# 50_VO-HDMI2_1_TX.net
KiCad netlist of a schematic drawn in Altium Designer
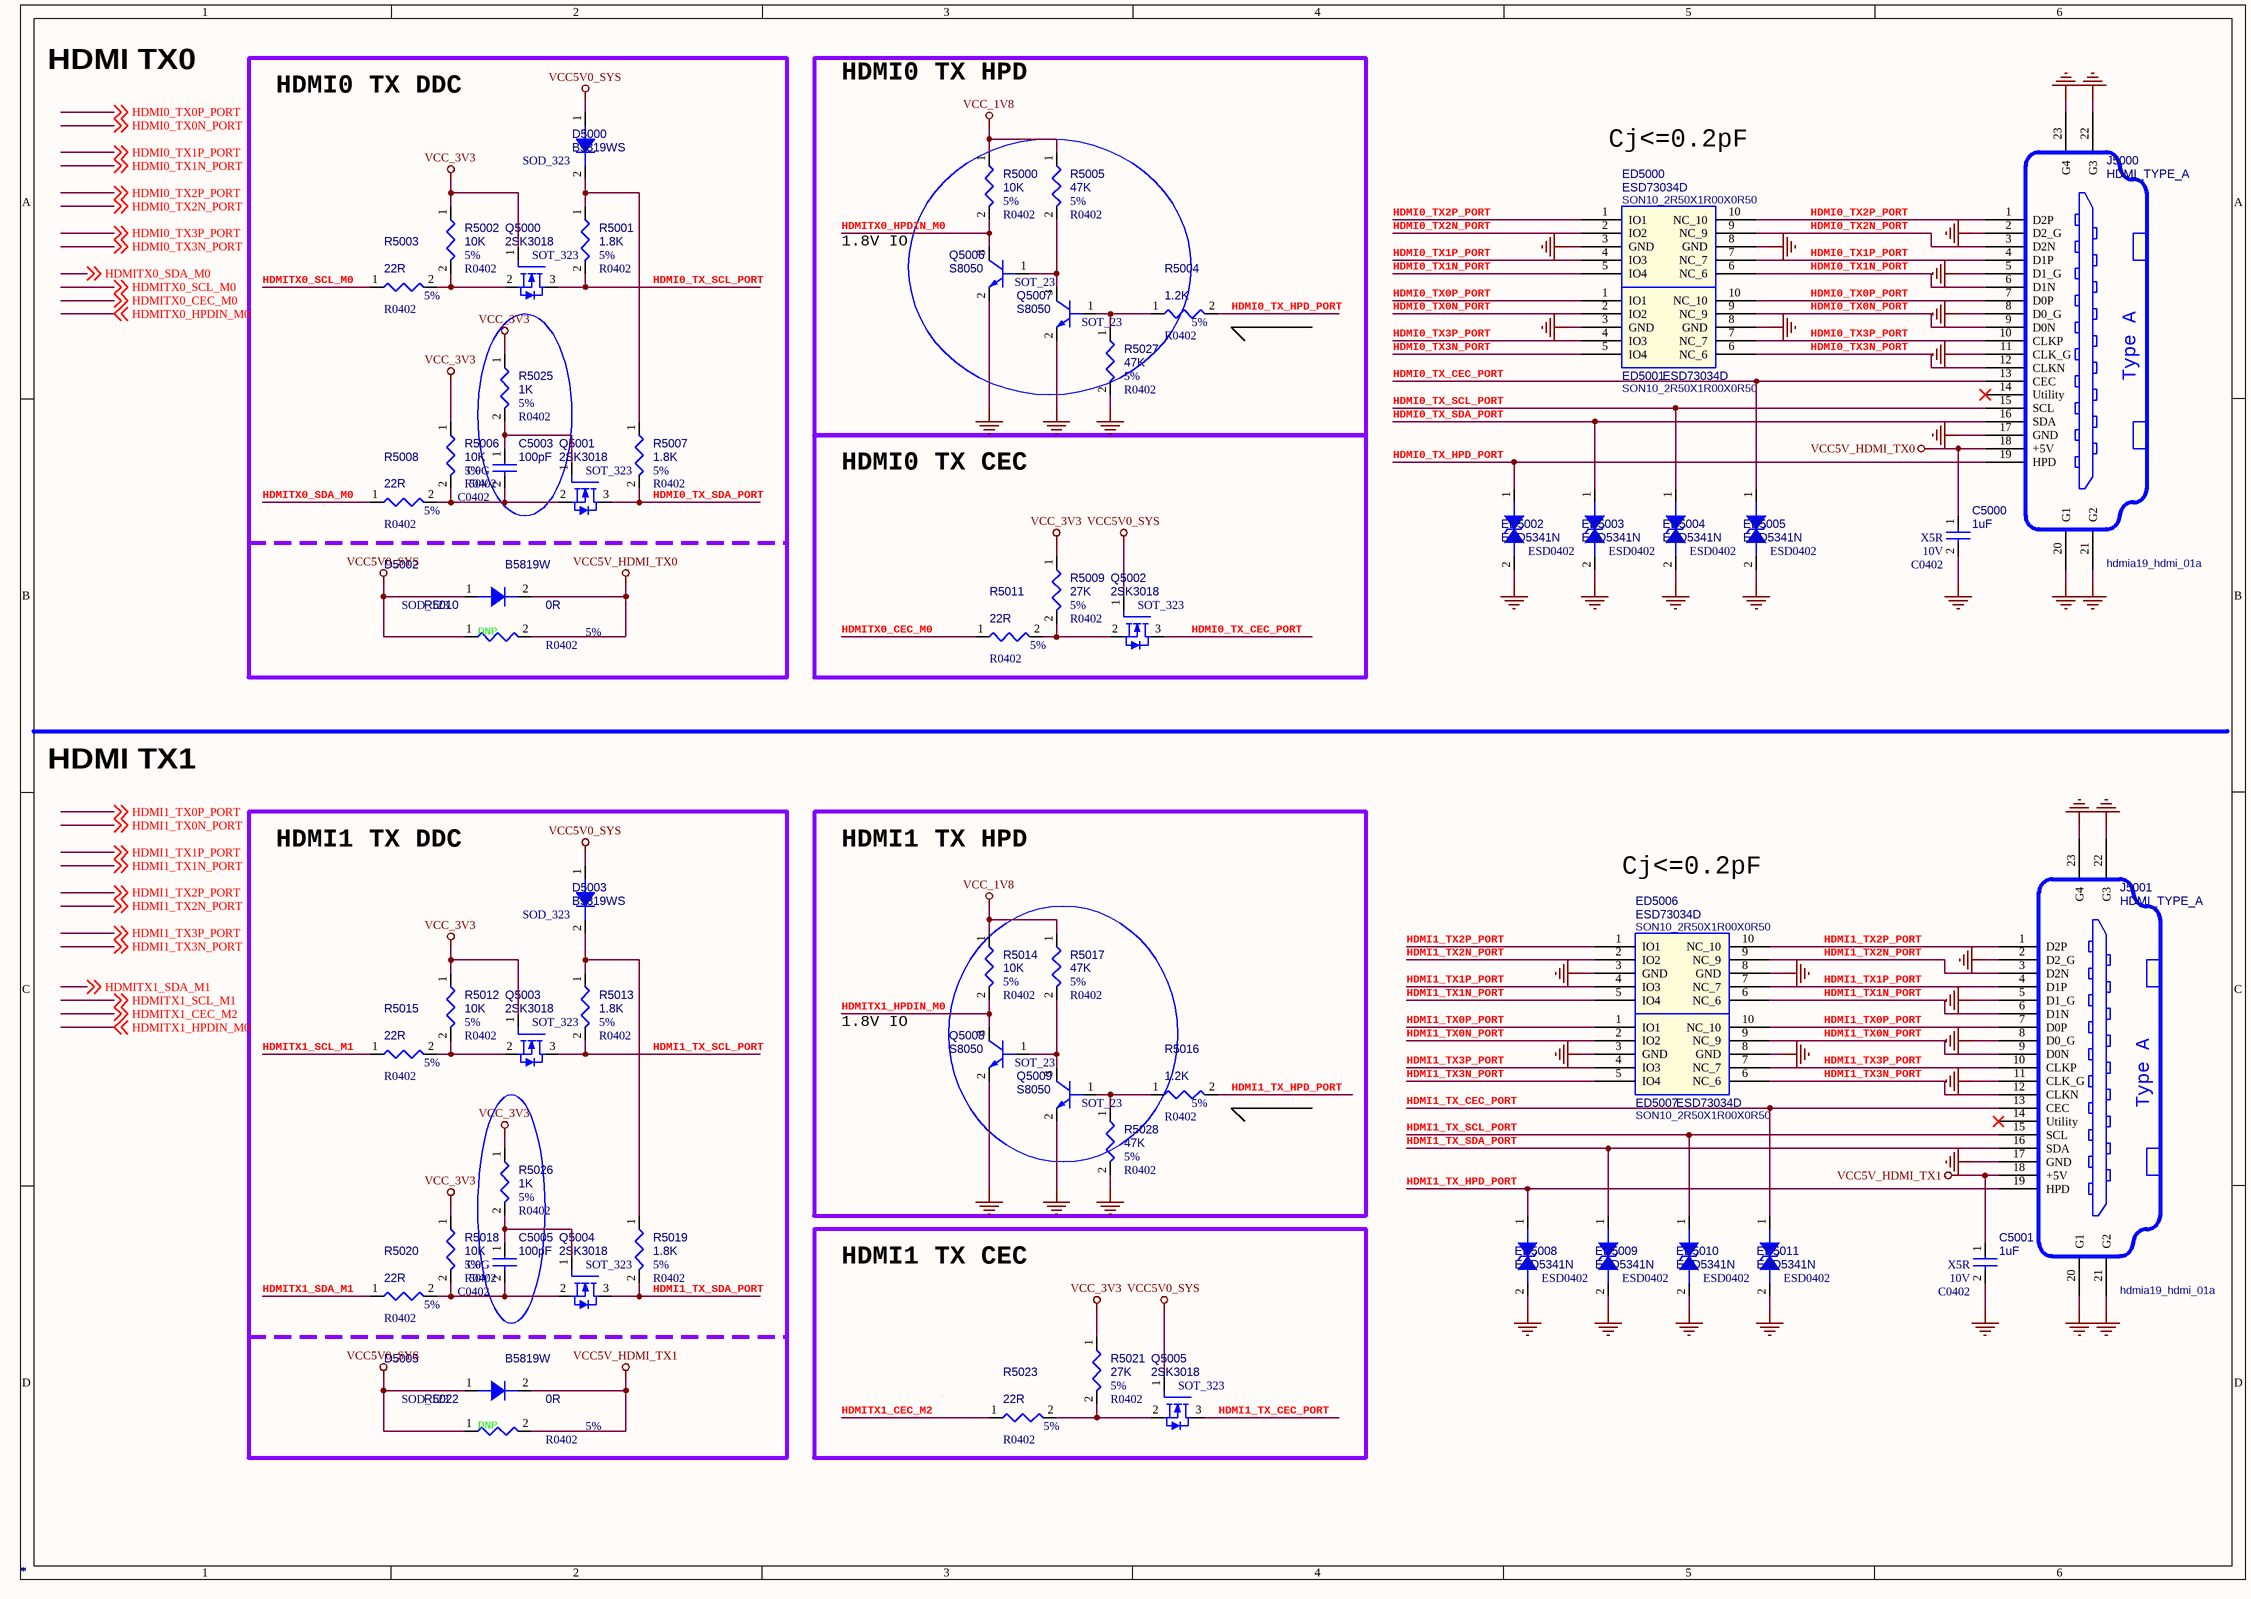
[diagram p0: 50.VO-HDMI2.1 TX.SchDoc]

(export (version "E")
  (design (tool "Eeschema 10.0.6"))
  (components
    (comp (ref "C5000")
      (value "*")
      (footprint "C0402")
      (description "cap,1.00uF,+/-10%,10V,X5R,C0402")
      (fields
        (field (name "VOLTAGE") "10V")
        (field (name "PCB FOOTPRINT") "C0402")
        (field (name "DIELECTRIC") "X5R")
        (field (name "MANUFACTURER") "TDK")
        (field (name "TOLERANCE") "10%")
        (field (name "ALTIUM_UNNAMED_1") "1uF")
        (field (name "CREATED BY") "JJJ")
      )
      (libsource (lib "*") (part "CAP NP"))
    )
    (comp (ref "C5001")
      (value "*")
      (footprint "C0402")
      (description "cap,1.00uF,+/-10%,10V,X5R,C0402")
      (fields
        (field (name "VOLTAGE") "10V")
        (field (name "PCB FOOTPRINT") "C0402")
        (field (name "DIELECTRIC") "X5R")
        (field (name "MANUFACTURER") "TDK")
        (field (name "TOLERANCE") "10%")
        (field (name "ALTIUM_UNNAMED_1") "1uF")
        (field (name "CREATED BY") "JJJ")
      )
      (libsource (lib "*") (part "CAP NP"))
    )
    (comp (ref "C5003")
      (value "*")
      (footprint "C0402")
      (description "cap,100.00pF,+/-10%,50V,C0G,C0402")
      (fields
        (field (name "VOLTAGE") "50V")
        (field (name "PCB FOOTPRINT") "C0402")
        (field (name "DIELECTRIC") "C0G")
        (field (name "TOLERANCE") "10%")
        (field (name "MANUFACTURER") "TDK")
        (field (name "ALTIUM_UNNAMED_1") "100pF")
        (field (name "CREATED BY") "JJJ")
      )
      (libsource (lib "*") (part "CAP NP"))
    )
    (comp (ref "C5005")
      (value "*")
      (footprint "C0402")
      (description "cap,100.00pF,+/-10%,50V,C0G,C0402")
      (fields
        (field (name "VOLTAGE") "50V")
        (field (name "PCB FOOTPRINT") "C0402")
        (field (name "DIELECTRIC") "C0G")
        (field (name "TOLERANCE") "10%")
        (field (name "MANUFACTURER") "TDK")
        (field (name "ALTIUM_UNNAMED_1") "100pF")
        (field (name "CREATED BY") "JJJ")
      )
      (libsource (lib "*") (part "CAP NP"))
    )
    (comp (ref "D5000")
      (value "*")
      (footprint "SOD_323")
      (description "Schottky BarrierЈ¬B5819WS SOD-323")
      (fields
        (field (name "PCB FOOTPRINT") "SOD_323")
        (field (name "MANUFACTURER") "і¤µз")
        (field (name "ALTIUM_UNNAMED_1") "B5819WS")
        (field (name "CREATED BY") "JJJ")
      )
      (libsource (lib "*") (part "DIODE"))
    )
    (comp (ref "D5002")
      (value "*")
      (footprint "SOD_123")
      (description "Schottky BarrierЈ¬B5819W SOD-123")
      (fields
        (field (name "PCB FOOTPRINT") "SOD_123")
        (field (name "MANUFACTURER") "і¤µз")
        (field (name "ALTIUM_UNNAMED_1") "B5819W")
        (field (name "CREATED BY") "JJJ")
      )
      (libsource (lib "*") (part "DIODE"))
    )
    (comp (ref "D5003")
      (value "*")
      (footprint "SOD_323")
      (description "Schottky BarrierЈ¬B5819WS SOD-323")
      (fields
        (field (name "PCB FOOTPRINT") "SOD_323")
        (field (name "MANUFACTURER") "і¤µз")
        (field (name "ALTIUM_UNNAMED_1") "B5819WS")
        (field (name "CREATED BY") "JJJ")
      )
      (libsource (lib "*") (part "DIODE"))
    )
    (comp (ref "D5005")
      (value "*")
      (footprint "SOD_123")
      (description "Schottky BarrierЈ¬B5819W SOD-123")
      (fields
        (field (name "PCB FOOTPRINT") "SOD_123")
        (field (name "MANUFACTURER") "і¤µз")
        (field (name "ALTIUM_UNNAMED_1") "B5819W")
        (field (name "CREATED BY") "JJJ")
      )
      (libsource (lib "*") (part "DIODE"))
    )
    (comp (ref "ED5000")
      (value "*")
      (footprint "SON10_2R50X1R00X0R50")
      (description "4-Lines, Uni-directional, Ultra-low Capacitance Transient Voltage Suppressors")
      (fields
        (field (name "PCB FOOTPRINT") "SON10_2R50X1R00X0R50")
        (field (name "MANUFACTURER") "WillSemi(О¤¶ы°лµјМе)")
        (field (name "ALTIUM_UNNAMED_1") "ESD73034D")
        (field (name "CREATED BY") "JJJ")
      )
      (libsource (lib "*") (part "ESD_ESD5304D"))
    )
    (comp (ref "ED5001")
      (value "*")
      (footprint "SON10_2R50X1R00X0R50")
      (description "4-Lines, Uni-directional, Ultra-low Capacitance Transient Voltage Suppressors")
      (fields
        (field (name "PCB FOOTPRINT") "SON10_2R50X1R00X0R50")
        (field (name "MANUFACTURER") "WillSemi(О¤¶ы°лµјМе)")
        (field (name "ALTIUM_UNNAMED_1") "ESD73034D")
        (field (name "CREATED BY") "JJJ")
      )
      (libsource (lib "*") (part "ESD_ESD5304D"))
    )
    (comp (ref "ED5002")
      (value "*")
      (footprint "ESD0402")
      (description "1-Line, Bi-directional, Transient Voltage Suppressors.1pF.")
      (fields
        (field (name "PCB FOOTPRINT") "ESD0402")
        (field (name "MANUFACTURER") "WillSemi(О¤¶ы°лµјМе)")
        (field (name "ALTIUM_UNNAMED_1") "ESD5341N")
        (field (name "CREATED BY") "JJJ")
      )
      (libsource (lib "*") (part "DIODE BI_DIR TRIG"))
    )
    (comp (ref "ED5003")
      (value "*")
      (footprint "ESD0402")
      (description "1-Line, Bi-directional, Transient Voltage Suppressors.1pF.")
      (fields
        (field (name "PCB FOOTPRINT") "ESD0402")
        (field (name "MANUFACTURER") "WillSemi(О¤¶ы°лµјМе)")
        (field (name "ALTIUM_UNNAMED_1") "ESD5341N")
        (field (name "CREATED BY") "JJJ")
      )
      (libsource (lib "*") (part "DIODE BI_DIR TRIG"))
    )
    (comp (ref "ED5004")
      (value "*")
      (footprint "ESD0402")
      (description "1-Line, Bi-directional, Transient Voltage Suppressors.1pF.")
      (fields
        (field (name "PCB FOOTPRINT") "ESD0402")
        (field (name "MANUFACTURER") "WillSemi(О¤¶ы°лµјМе)")
        (field (name "ALTIUM_UNNAMED_1") "ESD5341N")
        (field (name "CREATED BY") "JJJ")
      )
      (libsource (lib "*") (part "DIODE BI_DIR TRIG"))
    )
    (comp (ref "ED5005")
      (value "*")
      (footprint "ESD0402")
      (description "1-Line, Bi-directional, Transient Voltage Suppressors.1pF.")
      (fields
        (field (name "PCB FOOTPRINT") "ESD0402")
        (field (name "MANUFACTURER") "WillSemi(О¤¶ы°лµјМе)")
        (field (name "ALTIUM_UNNAMED_1") "ESD5341N")
        (field (name "CREATED BY") "JJJ")
      )
      (libsource (lib "*") (part "DIODE BI_DIR TRIG"))
    )
    (comp (ref "ED5006")
      (value "*")
      (footprint "SON10_2R50X1R00X0R50")
      (description "4-Lines, Uni-directional, Ultra-low Capacitance Transient Voltage Suppressors")
      (fields
        (field (name "PCB FOOTPRINT") "SON10_2R50X1R00X0R50")
        (field (name "MANUFACTURER") "WillSemi(О¤¶ы°лµјМе)")
        (field (name "ALTIUM_UNNAMED_1") "ESD73034D")
        (field (name "CREATED BY") "JJJ")
      )
      (libsource (lib "*") (part "ESD_ESD5304D"))
    )
    (comp (ref "ED5007")
      (value "*")
      (footprint "SON10_2R50X1R00X0R50")
      (description "4-Lines, Uni-directional, Ultra-low Capacitance Transient Voltage Suppressors")
      (fields
        (field (name "PCB FOOTPRINT") "SON10_2R50X1R00X0R50")
        (field (name "MANUFACTURER") "WillSemi(О¤¶ы°лµјМе)")
        (field (name "ALTIUM_UNNAMED_1") "ESD73034D")
        (field (name "CREATED BY") "JJJ")
      )
      (libsource (lib "*") (part "ESD_ESD5304D"))
    )
    (comp (ref "ED5008")
      (value "*")
      (footprint "ESD0402")
      (description "1-Line, Bi-directional, Transient Voltage Suppressors.1pF.")
      (fields
        (field (name "PCB FOOTPRINT") "ESD0402")
        (field (name "MANUFACTURER") "WillSemi(О¤¶ы°лµјМе)")
        (field (name "ALTIUM_UNNAMED_1") "ESD5341N")
        (field (name "CREATED BY") "JJJ")
      )
      (libsource (lib "*") (part "DIODE BI_DIR TRIG"))
    )
    (comp (ref "ED5009")
      (value "*")
      (footprint "ESD0402")
      (description "1-Line, Bi-directional, Transient Voltage Suppressors.1pF.")
      (fields
        (field (name "PCB FOOTPRINT") "ESD0402")
        (field (name "MANUFACTURER") "WillSemi(О¤¶ы°лµјМе)")
        (field (name "ALTIUM_UNNAMED_1") "ESD5341N")
        (field (name "CREATED BY") "JJJ")
      )
      (libsource (lib "*") (part "DIODE BI_DIR TRIG"))
    )
    (comp (ref "ED5010")
      (value "*")
      (footprint "ESD0402")
      (description "1-Line, Bi-directional, Transient Voltage Suppressors.1pF.")
      (fields
        (field (name "PCB FOOTPRINT") "ESD0402")
        (field (name "MANUFACTURER") "WillSemi(О¤¶ы°лµјМе)")
        (field (name "ALTIUM_UNNAMED_1") "ESD5341N")
        (field (name "CREATED BY") "JJJ")
      )
      (libsource (lib "*") (part "DIODE BI_DIR TRIG"))
    )
    (comp (ref "ED5011")
      (value "*")
      (footprint "ESD0402")
      (description "1-Line, Bi-directional, Transient Voltage Suppressors.1pF.")
      (fields
        (field (name "PCB FOOTPRINT") "ESD0402")
        (field (name "MANUFACTURER") "WillSemi(О¤¶ы°лµјМе)")
        (field (name "ALTIUM_UNNAMED_1") "ESD5341N")
        (field (name "CREATED BY") "JJJ")
      )
      (libsource (lib "*") (part "DIODE BI_DIR TRIG"))
    )
    (comp (ref "J5000")
      (value "*")
      (footprint "hdmia19_hdmi_01a")
      (fields
        (field (name "PCB FOOTPRINT") "hdmia19_hdmi_01a")
        (field (name "ALTIUM_UNNAMED_1") "HDMI_TYPE_A")
      )
      (libsource (lib "*") (part "HDMI_TYPE_A_0"))
    )
    (comp (ref "J5001")
      (value "*")
      (footprint "hdmia19_hdmi_01a")
      (fields
        (field (name "PCB FOOTPRINT") "hdmia19_hdmi_01a")
        (field (name "ALTIUM_UNNAMED_1") "HDMI_TYPE_A")
      )
      (libsource (lib "*") (part "HDMI_TYPE_A_0"))
    )
    (comp (ref "Q5000")
      (value "*")
      (footprint "SOT23")
      (description "NMOS,2SK3018,SOT_323,Id=0.1A,Vds=30V")
      (fields
        (field (name "PCB FOOTPRINT") "SOT_323")
        (field (name "MANUFACTURER") "ROHM")
        (field (name "ALTIUM_UNNAMED_1") "2SK3018")
        (field (name "CREATED BY") "JJJ")
      )
      (libsource (lib "*") (part "MOSFET N"))
    )
    (comp (ref "Q5001")
      (value "*")
      (footprint "SOT23")
      (description "NMOS,2SK3018,SOT_323,Id=0.1A,Vds=30V")
      (fields
        (field (name "PCB FOOTPRINT") "SOT_323")
        (field (name "MANUFACTURER") "ROHM")
        (field (name "ALTIUM_UNNAMED_1") "2SK3018")
        (field (name "CREATED BY") "JJJ")
      )
      (libsource (lib "*") (part "MOSFET N"))
    )
    (comp (ref "Q5002")
      (value "*")
      (footprint "SOT23")
      (description "NMOS,2SK3018,SOT_323,Id=0.1A,Vds=30V")
      (fields
        (field (name "PCB FOOTPRINT") "SOT_323")
        (field (name "MANUFACTURER") "ROHM")
        (field (name "ALTIUM_UNNAMED_1") "2SK3018")
        (field (name "CREATED BY") "JJJ")
      )
      (libsource (lib "*") (part "MOSFET N"))
    )
    (comp (ref "Q5003")
      (value "*")
      (footprint "SOT23")
      (description "NMOS,2SK3018,SOT_323,Id=0.1A,Vds=30V")
      (fields
        (field (name "PCB FOOTPRINT") "SOT_323")
        (field (name "MANUFACTURER") "ROHM")
        (field (name "ALTIUM_UNNAMED_1") "2SK3018")
        (field (name "CREATED BY") "JJJ")
      )
      (libsource (lib "*") (part "MOSFET N"))
    )
    (comp (ref "Q5004")
      (value "*")
      (footprint "SOT23")
      (description "NMOS,2SK3018,SOT_323,Id=0.1A,Vds=30V")
      (fields
        (field (name "PCB FOOTPRINT") "SOT_323")
        (field (name "MANUFACTURER") "ROHM")
        (field (name "ALTIUM_UNNAMED_1") "2SK3018")
        (field (name "CREATED BY") "JJJ")
      )
      (libsource (lib "*") (part "MOSFET N"))
    )
    (comp (ref "Q5005")
      (value "*")
      (footprint "SOT23")
      (description "NMOS,2SK3018,SOT_323,Id=0.1A,Vds=30V")
      (fields
        (field (name "PCB FOOTPRINT") "SOT_323")
        (field (name "MANUFACTURER") "ROHM")
        (field (name "ALTIUM_UNNAMED_1") "2SK3018")
        (field (name "CREATED BY") "JJJ")
      )
      (libsource (lib "*") (part "MOSFET N"))
    )
    (comp (ref "Q5006")
      (value "*")
      (footprint "SOT_23")
      (description "S8050,SOT23")
      (fields
        (field (name "PCB FOOTPRINT") "SOT_23")
        (field (name "MANUFACTURER") "і¤µз")
        (field (name "ALTIUM_UNNAMED_1") "S8050")
        (field (name "CREATED BY") "JJJ")
      )
      (libsource (lib "*") (part "NPN"))
    )
    (comp (ref "Q5007")
      (value "*")
      (footprint "SOT_23")
      (description "S8050,SOT23")
      (fields
        (field (name "PCB FOOTPRINT") "SOT_23")
        (field (name "MANUFACTURER") "і¤µз")
        (field (name "ALTIUM_UNNAMED_1") "S8050")
        (field (name "CREATED BY") "JJJ")
      )
      (libsource (lib "*") (part "NPN"))
    )
    (comp (ref "Q5008")
      (value "*")
      (footprint "SOT_23")
      (description "S8050,SOT23")
      (fields
        (field (name "PCB FOOTPRINT") "SOT_23")
        (field (name "MANUFACTURER") "і¤µз")
        (field (name "ALTIUM_UNNAMED_1") "S8050")
        (field (name "CREATED BY") "JJJ")
      )
      (libsource (lib "*") (part "NPN"))
    )
    (comp (ref "Q5009")
      (value "*")
      (footprint "SOT_23")
      (description "S8050,SOT23")
      (fields
        (field (name "PCB FOOTPRINT") "SOT_23")
        (field (name "MANUFACTURER") "і¤µз")
        (field (name "ALTIUM_UNNAMED_1") "S8050")
        (field (name "CREATED BY") "JJJ")
      )
      (libsource (lib "*") (part "NPN"))
    )
    (comp (ref "R5000")
      (value "*")
      (footprint "R0402")
      (description "НЁУГєсД¤µзЧи,10K,+/-5%,R0402,1/16W.")
      (fields
        (field (name "PCB FOOTPRINT") "R0402")
        (field (name "TOLERANCE") "5%")
        (field (name "MANUFACTURER") "YAGEO")
        (field (name "ALTIUM_UNNAMED_1") "10K")
        (field (name "CREATED BY") "YTL")
      )
      (libsource (lib "*") (part "RESISTOR_Dup1"))
    )
    (comp (ref "R5001")
      (value "*")
      (footprint "R0402")
      (description "НЁУГєсД¤µзЧи,1K8,+/-5%,R0402,1/16W.")
      (fields
        (field (name "PCB FOOTPRINT") "R0402")
        (field (name "TOLERANCE") "5%")
        (field (name "MANUFACTURER") "YAGEO")
        (field (name "ALTIUM_UNNAMED_1") "1.8K")
        (field (name "CREATED BY") "YTL")
      )
      (libsource (lib "*") (part "RESISTOR_Dup1"))
    )
    (comp (ref "R5002")
      (value "*")
      (footprint "R0402")
      (description "НЁУГєсД¤µзЧи,10K,+/-5%,R0402,1/16W.")
      (fields
        (field (name "PCB FOOTPRINT") "R0402")
        (field (name "TOLERANCE") "5%")
        (field (name "MANUFACTURER") "YAGEO")
        (field (name "ALTIUM_UNNAMED_1") "10K")
        (field (name "CREATED BY") "YTL")
      )
      (libsource (lib "*") (part "RESISTOR_Dup1"))
    )
    (comp (ref "R5003")
      (value "*")
      (footprint "R0402")
      (description "НЁУГєсД¤µзЧи,22R,+/-5%,R0402,1/16W.")
      (fields
        (field (name "PCB FOOTPRINT") "R0402")
        (field (name "TOLERANCE") "5%")
        (field (name "MANUFACTURER") "YAGEO")
        (field (name "ALTIUM_UNNAMED_1") "22R")
        (field (name "CREATED BY") "YTL")
      )
      (libsource (lib "*") (part "RESISTOR_Dup1"))
    )
    (comp (ref "R5004")
      (value "*")
      (footprint "R0402")
      (description "НЁУГєсД¤µзЧи,1K2,+/-5%,R0402,1/16W.")
      (fields
        (field (name "PCB FOOTPRINT") "R0402")
        (field (name "TOLERANCE") "5%")
        (field (name "MANUFACTURER") "YAGEO")
        (field (name "ALTIUM_UNNAMED_1") "1.2K")
        (field (name "CREATED BY") "YTL")
      )
      (libsource (lib "*") (part "RESISTOR_Dup1"))
    )
    (comp (ref "R5005")
      (value "*")
      (footprint "R0402")
      (description "НЁУГєсД¤µзЧи,47K,+/-5%,R0402,1/16W.")
      (fields
        (field (name "PCB FOOTPRINT") "R0402")
        (field (name "TOLERANCE") "5%")
        (field (name "MANUFACTURER") "YAGEO")
        (field (name "ALTIUM_UNNAMED_1") "47K")
        (field (name "CREATED BY") "YTL")
      )
      (libsource (lib "*") (part "RESISTOR_Dup1"))
    )
    (comp (ref "R5006")
      (value "*")
      (footprint "R0402")
      (description "НЁУГєсД¤µзЧи,10K,+/-5%,R0402,1/16W.")
      (fields
        (field (name "PCB FOOTPRINT") "R0402")
        (field (name "TOLERANCE") "5%")
        (field (name "MANUFACTURER") "YAGEO")
        (field (name "ALTIUM_UNNAMED_1") "10K")
        (field (name "CREATED BY") "YTL")
      )
      (libsource (lib "*") (part "RESISTOR_Dup1"))
    )
    (comp (ref "R5007")
      (value "*")
      (footprint "R0402")
      (description "НЁУГєсД¤µзЧи,1K8,+/-5%,R0402,1/16W.")
      (fields
        (field (name "PCB FOOTPRINT") "R0402")
        (field (name "TOLERANCE") "5%")
        (field (name "MANUFACTURER") "YAGEO")
        (field (name "ALTIUM_UNNAMED_1") "1.8K")
        (field (name "CREATED BY") "YTL")
      )
      (libsource (lib "*") (part "RESISTOR_Dup1"))
    )
    (comp (ref "R5008")
      (value "*")
      (footprint "R0402")
      (description "НЁУГєсД¤µзЧи,22R,+/-5%,R0402,1/16W.")
      (fields
        (field (name "PCB FOOTPRINT") "R0402")
        (field (name "TOLERANCE") "5%")
        (field (name "MANUFACTURER") "YAGEO")
        (field (name "ALTIUM_UNNAMED_1") "22R")
        (field (name "CREATED BY") "YTL")
      )
      (libsource (lib "*") (part "RESISTOR_Dup1"))
    )
    (comp (ref "R5009")
      (value "*")
      (footprint "R0402")
      (description "НЁУГєсД¤µзЧи,27K,+/-5%,R0402,1/16W.")
      (fields
        (field (name "PCB FOOTPRINT") "R0402")
        (field (name "TOLERANCE") "5%")
        (field (name "MANUFACTURER") "YAGEO")
        (field (name "ALTIUM_UNNAMED_1") "27K")
        (field (name "CREATED BY") "YTL")
      )
      (libsource (lib "*") (part "RESISTOR_Dup1"))
    )
    (comp (ref "R5010")
      (value "*")
      (footprint "R0402")
      (description "НЁУГєсД¤µзЧи,0R,+/-5%,R0402,1/16W.")
      (fields
        (field (name "PCB FOOTPRINT") "R0402")
        (field (name "TOLERANCE") "5%")
        (field (name "OPTION") "DNP")
        (field (name "MANUFACTURER") "YAGEO")
        (field (name "ALTIUM_UNNAMED_1") "0R")
        (field (name "CREATED BY") "YTL")
      )
      (libsource (lib "*") (part "RESISTOR_Dup1"))
    )
    (comp (ref "R5011")
      (value "*")
      (footprint "R0402")
      (description "НЁУГєсД¤µзЧи,22R,+/-5%,R0402,1/16W.")
      (fields
        (field (name "PCB FOOTPRINT") "R0402")
        (field (name "TOLERANCE") "5%")
        (field (name "MANUFACTURER") "YAGEO")
        (field (name "ALTIUM_UNNAMED_1") "22R")
        (field (name "CREATED BY") "YTL")
      )
      (libsource (lib "*") (part "RESISTOR_Dup1"))
    )
    (comp (ref "R5012")
      (value "*")
      (footprint "R0402")
      (description "НЁУГєсД¤µзЧи,10K,+/-5%,R0402,1/16W.")
      (fields
        (field (name "PCB FOOTPRINT") "R0402")
        (field (name "TOLERANCE") "5%")
        (field (name "MANUFACTURER") "YAGEO")
        (field (name "ALTIUM_UNNAMED_1") "10K")
        (field (name "CREATED BY") "YTL")
      )
      (libsource (lib "*") (part "RESISTOR_Dup1"))
    )
    (comp (ref "R5013")
      (value "*")
      (footprint "R0402")
      (description "НЁУГєсД¤µзЧи,1K8,+/-5%,R0402,1/16W.")
      (fields
        (field (name "PCB FOOTPRINT") "R0402")
        (field (name "TOLERANCE") "5%")
        (field (name "MANUFACTURER") "YAGEO")
        (field (name "ALTIUM_UNNAMED_1") "1.8K")
        (field (name "CREATED BY") "YTL")
      )
      (libsource (lib "*") (part "RESISTOR_Dup1"))
    )
    (comp (ref "R5014")
      (value "*")
      (footprint "R0402")
      (description "НЁУГєсД¤µзЧи,10K,+/-5%,R0402,1/16W.")
      (fields
        (field (name "PCB FOOTPRINT") "R0402")
        (field (name "TOLERANCE") "5%")
        (field (name "MANUFACTURER") "YAGEO")
        (field (name "ALTIUM_UNNAMED_1") "10K")
        (field (name "CREATED BY") "YTL")
      )
      (libsource (lib "*") (part "RESISTOR_Dup1"))
    )
    (comp (ref "R5015")
      (value "*")
      (footprint "R0402")
      (description "НЁУГєсД¤µзЧи,22R,+/-5%,R0402,1/16W.")
      (fields
        (field (name "PCB FOOTPRINT") "R0402")
        (field (name "TOLERANCE") "5%")
        (field (name "MANUFACTURER") "YAGEO")
        (field (name "ALTIUM_UNNAMED_1") "22R")
        (field (name "CREATED BY") "YTL")
      )
      (libsource (lib "*") (part "RESISTOR_Dup1"))
    )
    (comp (ref "R5016")
      (value "*")
      (footprint "R0402")
      (description "НЁУГєсД¤µзЧи,1K2,+/-5%,R0402,1/16W.")
      (fields
        (field (name "PCB FOOTPRINT") "R0402")
        (field (name "TOLERANCE") "5%")
        (field (name "MANUFACTURER") "YAGEO")
        (field (name "ALTIUM_UNNAMED_1") "1.2K")
        (field (name "CREATED BY") "YTL")
      )
      (libsource (lib "*") (part "RESISTOR_Dup1"))
    )
    (comp (ref "R5017")
      (value "*")
      (footprint "R0402")
      (description "НЁУГєсД¤µзЧи,47K,+/-5%,R0402,1/16W.")
      (fields
        (field (name "PCB FOOTPRINT") "R0402")
        (field (name "TOLERANCE") "5%")
        (field (name "MANUFACTURER") "YAGEO")
        (field (name "ALTIUM_UNNAMED_1") "47K")
        (field (name "CREATED BY") "YTL")
      )
      (libsource (lib "*") (part "RESISTOR_Dup1"))
    )
    (comp (ref "R5018")
      (value "*")
      (footprint "R0402")
      (description "НЁУГєсД¤µзЧи,10K,+/-5%,R0402,1/16W.")
      (fields
        (field (name "PCB FOOTPRINT") "R0402")
        (field (name "TOLERANCE") "5%")
        (field (name "MANUFACTURER") "YAGEO")
        (field (name "ALTIUM_UNNAMED_1") "10K")
        (field (name "CREATED BY") "YTL")
      )
      (libsource (lib "*") (part "RESISTOR_Dup1"))
    )
    (comp (ref "R5019")
      (value "*")
      (footprint "R0402")
      (description "НЁУГєсД¤µзЧи,1K8,+/-5%,R0402,1/16W.")
      (fields
        (field (name "PCB FOOTPRINT") "R0402")
        (field (name "TOLERANCE") "5%")
        (field (name "MANUFACTURER") "YAGEO")
        (field (name "ALTIUM_UNNAMED_1") "1.8K")
        (field (name "CREATED BY") "YTL")
      )
      (libsource (lib "*") (part "RESISTOR_Dup1"))
    )
    (comp (ref "R5020")
      (value "*")
      (footprint "R0402")
      (description "НЁУГєсД¤µзЧи,22R,+/-5%,R0402,1/16W.")
      (fields
        (field (name "PCB FOOTPRINT") "R0402")
        (field (name "TOLERANCE") "5%")
        (field (name "MANUFACTURER") "YAGEO")
        (field (name "ALTIUM_UNNAMED_1") "22R")
        (field (name "CREATED BY") "YTL")
      )
      (libsource (lib "*") (part "RESISTOR_Dup1"))
    )
    (comp (ref "R5021")
      (value "*")
      (footprint "R0402")
      (description "НЁУГєсД¤µзЧи,27K,+/-5%,R0402,1/16W.")
      (fields
        (field (name "PCB FOOTPRINT") "R0402")
        (field (name "TOLERANCE") "5%")
        (field (name "MANUFACTURER") "YAGEO")
        (field (name "ALTIUM_UNNAMED_1") "27K")
        (field (name "CREATED BY") "YTL")
      )
      (libsource (lib "*") (part "RESISTOR_Dup1"))
    )
    (comp (ref "R5022")
      (value "*")
      (footprint "R0402")
      (description "НЁУГєсД¤µзЧи,0R,+/-5%,R0402,1/16W.")
      (fields
        (field (name "PCB FOOTPRINT") "R0402")
        (field (name "TOLERANCE") "5%")
        (field (name "OPTION") "DNP")
        (field (name "MANUFACTURER") "YAGEO")
        (field (name "ALTIUM_UNNAMED_1") "0R")
        (field (name "CREATED BY") "YTL")
      )
      (libsource (lib "*") (part "RESISTOR_Dup1"))
    )
    (comp (ref "R5023")
      (value "*")
      (footprint "R0402")
      (description "НЁУГєсД¤µзЧи,22R,+/-5%,R0402,1/16W.")
      (fields
        (field (name "PCB FOOTPRINT") "R0402")
        (field (name "TOLERANCE") "5%")
        (field (name "MANUFACTURER") "YAGEO")
        (field (name "ALTIUM_UNNAMED_1") "22R")
        (field (name "CREATED BY") "YTL")
      )
      (libsource (lib "*") (part "RESISTOR_Dup1"))
    )
    (comp (ref "R5025")
      (value "*")
      (footprint "R0402")
      (description "НЁУГєсД¤µзЧи,1K,+/-5%,R0402,1/16W.")
      (fields
        (field (name "PCB FOOTPRINT") "R0402")
        (field (name "TOLERANCE") "5%")
        (field (name "MANUFACTURER") "YAGEO")
        (field (name "ALTIUM_UNNAMED_1") "1K")
        (field (name "CREATED BY") "YTL")
      )
      (libsource (lib "*") (part "RESISTOR_Dup1"))
    )
    (comp (ref "R5026")
      (value "*")
      (footprint "R0402")
      (description "НЁУГєсД¤µзЧи,1K,+/-5%,R0402,1/16W.")
      (fields
        (field (name "PCB FOOTPRINT") "R0402")
        (field (name "TOLERANCE") "5%")
        (field (name "MANUFACTURER") "YAGEO")
        (field (name "ALTIUM_UNNAMED_1") "1K")
        (field (name "CREATED BY") "YTL")
      )
      (libsource (lib "*") (part "RESISTOR_Dup1"))
    )
    (comp (ref "R5027")
      (value "*")
      (footprint "R0402")
      (description "НЁУГєсД¤µзЧи,47K,+/-5%,R0402,1/16W.")
      (fields
        (field (name "PCB FOOTPRINT") "R0402")
        (field (name "TOLERANCE") "5%")
        (field (name "MANUFACTURER") "YAGEO")
        (field (name "ALTIUM_UNNAMED_1") "47K")
        (field (name "CREATED BY") "YTL")
      )
      (libsource (lib "*") (part "RESISTOR_Dup1"))
    )
    (comp (ref "R5028")
      (value "*")
      (footprint "R0402")
      (description "НЁУГєсД¤µзЧи,47K,+/-5%,R0402,1/16W.")
      (fields
        (field (name "PCB FOOTPRINT") "R0402")
        (field (name "TOLERANCE") "5%")
        (field (name "MANUFACTURER") "YAGEO")
        (field (name "ALTIUM_UNNAMED_1") "47K")
        (field (name "CREATED BY") "YTL")
      )
      (libsource (lib "*") (part "RESISTOR_Dup1"))
    )
  )
  (nets
    (net (code "1") (name "/HDMI0_TX_CEC_PORT") (class "Default")
      (node (ref "ED5005") (pin "1") (pinfunction "1_1") (pintype "passive"))
      (node (ref "J5000") (pin "13") (pinfunction "CEC_13") (pintype "passive"))
      (node (ref "Q5002") (pin "3") (pinfunction "DRAIN_3") (pintype "passive"))
    )
    (net (code "2") (name "/HDMI0_TX_HPD_PORT") (class "Default")
      (node (ref "ED5002") (pin "1") (pinfunction "1_1") (pintype "passive"))
      (node (ref "J5000") (pin "19") (pinfunction "HPD_19") (pintype "passive"))
      (node (ref "R5004") (pin "2") (pinfunction "2_2") (pintype "passive"))
    )
    (net (code "3") (name "/HDMI0_TX_SCL_PORT") (class "Default")
      (node (ref "ED5004") (pin "1") (pinfunction "1_1") (pintype "passive"))
      (node (ref "J5000") (pin "15") (pinfunction "SCL_15") (pintype "passive"))
      (node (ref "Q5000") (pin "3") (pinfunction "DRAIN_3") (pintype "passive"))
      (node (ref "R5001") (pin "2") (pinfunction "2_2") (pintype "passive"))
    )
    (net (code "4") (name "/HDMI0_TX_SDA_PORT") (class "Default")
      (node (ref "ED5003") (pin "1") (pinfunction "1_1") (pintype "passive"))
      (node (ref "J5000") (pin "16") (pinfunction "SDA_16") (pintype "passive"))
      (node (ref "Q5001") (pin "3") (pinfunction "DRAIN_3") (pintype "passive"))
      (node (ref "R5007") (pin "2") (pinfunction "2_2") (pintype "passive"))
    )
    (net (code "5") (name "/HDMI1_TX_CEC_PORT") (class "Default")
      (node (ref "ED5011") (pin "1") (pinfunction "1_1") (pintype "passive"))
      (node (ref "J5001") (pin "13") (pinfunction "CEC_13") (pintype "passive"))
      (node (ref "Q5005") (pin "3") (pinfunction "DRAIN_3") (pintype "passive"))
    )
    (net (code "6") (name "/HDMI1_TX_HPD_PORT") (class "Default")
      (node (ref "ED5008") (pin "1") (pinfunction "1_1") (pintype "passive"))
      (node (ref "J5001") (pin "19") (pinfunction "HPD_19") (pintype "passive"))
      (node (ref "R5016") (pin "2") (pinfunction "2_2") (pintype "passive"))
    )
    (net (code "7") (name "/HDMI1_TX_SCL_PORT") (class "Default")
      (node (ref "ED5010") (pin "1") (pinfunction "1_1") (pintype "passive"))
      (node (ref "J5001") (pin "15") (pinfunction "SCL_15") (pintype "passive"))
      (node (ref "Q5003") (pin "3") (pinfunction "DRAIN_3") (pintype "passive"))
      (node (ref "R5013") (pin "2") (pinfunction "2_2") (pintype "passive"))
    )
    (net (code "8") (name "/HDMI1_TX_SDA_PORT") (class "Default")
      (node (ref "ED5009") (pin "1") (pinfunction "1_1") (pintype "passive"))
      (node (ref "J5001") (pin "16") (pinfunction "SDA_16") (pintype "passive"))
      (node (ref "Q5004") (pin "3") (pinfunction "DRAIN_3") (pintype "passive"))
      (node (ref "R5019") (pin "2") (pinfunction "2_2") (pintype "passive"))
    )
    (net (code "9") (name "GND") (class "Default")
      (node (ref "C5000") (pin "2") (pinfunction "2_2") (pintype "passive"))
      (node (ref "C5001") (pin "2") (pinfunction "2_2") (pintype "passive"))
      (node (ref "ED5000") (pin "3") (pinfunction "GND_3") (pintype "power_in"))
      (node (ref "ED5000") (pin "8") (pinfunction "GND_8") (pintype "power_in"))
      (node (ref "ED5001") (pin "3") (pinfunction "GND_3") (pintype "power_in"))
      (node (ref "ED5001") (pin "8") (pinfunction "GND_8") (pintype "power_in"))
      (node (ref "ED5002") (pin "2") (pinfunction "2_2") (pintype "passive"))
      (node (ref "ED5003") (pin "2") (pinfunction "2_2") (pintype "passive"))
      (node (ref "ED5004") (pin "2") (pinfunction "2_2") (pintype "passive"))
      (node (ref "ED5005") (pin "2") (pinfunction "2_2") (pintype "passive"))
      (node (ref "ED5006") (pin "3") (pinfunction "GND_3") (pintype "power_in"))
      (node (ref "ED5006") (pin "8") (pinfunction "GND_8") (pintype "power_in"))
      (node (ref "ED5007") (pin "3") (pinfunction "GND_3") (pintype "power_in"))
      (node (ref "ED5007") (pin "8") (pinfunction "GND_8") (pintype "power_in"))
      (node (ref "ED5008") (pin "2") (pinfunction "2_2") (pintype "passive"))
      (node (ref "ED5009") (pin "2") (pinfunction "2_2") (pintype "passive"))
      (node (ref "ED5010") (pin "2") (pinfunction "2_2") (pintype "passive"))
      (node (ref "ED5011") (pin "2") (pinfunction "2_2") (pintype "passive"))
      (node (ref "J5000") (pin "11") (pinfunction "CLK_G_11") (pintype "passive"))
      (node (ref "J5000") (pin "17") (pinfunction "GND_17") (pintype "passive"))
      (node (ref "J5000") (pin "2") (pinfunction "D2_G_2") (pintype "passive"))
      (node (ref "J5000") (pin "20") (pinfunction "G1_20") (pintype "passive"))
      (node (ref "J5000") (pin "21") (pinfunction "G2_21") (pintype "passive"))
      (node (ref "J5000") (pin "22") (pinfunction "G3_22") (pintype "passive"))
      (node (ref "J5000") (pin "23") (pinfunction "G4_23") (pintype "passive"))
      (node (ref "J5000") (pin "5") (pinfunction "D1_G_5") (pintype "passive"))
      (node (ref "J5000") (pin "8") (pinfunction "D0_G_8") (pintype "passive"))
      (node (ref "J5001") (pin "11") (pinfunction "CLK_G_11") (pintype "passive"))
      (node (ref "J5001") (pin "17") (pinfunction "GND_17") (pintype "passive"))
      (node (ref "J5001") (pin "2") (pinfunction "D2_G_2") (pintype "passive"))
      (node (ref "J5001") (pin "20") (pinfunction "G1_20") (pintype "passive"))
      (node (ref "J5001") (pin "21") (pinfunction "G2_21") (pintype "passive"))
      (node (ref "J5001") (pin "22") (pinfunction "G3_22") (pintype "passive"))
      (node (ref "J5001") (pin "23") (pinfunction "G4_23") (pintype "passive"))
      (node (ref "J5001") (pin "5") (pinfunction "D1_G_5") (pintype "passive"))
      (node (ref "J5001") (pin "8") (pinfunction "D0_G_8") (pintype "passive"))
      (node (ref "Q5006") (pin "2") (pinfunction "EMITTER_2") (pintype "passive"))
      (node (ref "Q5007") (pin "2") (pinfunction "EMITTER_2") (pintype "passive"))
      (node (ref "Q5008") (pin "2") (pinfunction "EMITTER_2") (pintype "passive"))
      (node (ref "Q5009") (pin "2") (pinfunction "EMITTER_2") (pintype "passive"))
      (node (ref "R5027") (pin "2") (pinfunction "2_2") (pintype "passive"))
      (node (ref "R5028") (pin "2") (pinfunction "2_2") (pintype "passive"))
    )
    (net (code "10") (name "HDMI0_TX0N_PORT") (class "Default")
      (node (ref "ED5001") (pin "2") (pinfunction "IO2_2") (pintype "passive"))
      (node (ref "ED5001") (pin "9") (pinfunction "NC_9_9") (pintype "passive"))
      (node (ref "J5000") (pin "9") (pinfunction "D0N_9") (pintype "passive"))
    )
    (net (code "11") (name "HDMI0_TX0P_PORT") (class "Default")
      (node (ref "ED5001") (pin "1") (pinfunction "IO1_1") (pintype "passive"))
      (node (ref "ED5001") (pin "10") (pinfunction "NC_10_10") (pintype "passive"))
      (node (ref "J5000") (pin "7") (pinfunction "D0P_7") (pintype "passive"))
    )
    (net (code "12") (name "HDMI0_TX1N_PORT") (class "Default")
      (node (ref "ED5000") (pin "5") (pinfunction "IO4_5") (pintype "passive"))
      (node (ref "ED5000") (pin "6") (pinfunction "NC_6_6") (pintype "passive"))
      (node (ref "J5000") (pin "6") (pinfunction "D1N_6") (pintype "passive"))
    )
    (net (code "13") (name "HDMI0_TX1P_PORT") (class "Default")
      (node (ref "ED5000") (pin "4") (pinfunction "IO3_4") (pintype "passive"))
      (node (ref "ED5000") (pin "7") (pinfunction "NC_7_7") (pintype "passive"))
      (node (ref "J5000") (pin "4") (pinfunction "D1P_4") (pintype "passive"))
    )
    (net (code "14") (name "HDMI0_TX2N_PORT") (class "Default")
      (node (ref "ED5000") (pin "2") (pinfunction "IO2_2") (pintype "passive"))
      (node (ref "ED5000") (pin "9") (pinfunction "NC_9_9") (pintype "passive"))
      (node (ref "J5000") (pin "3") (pinfunction "D2N_3") (pintype "passive"))
    )
    (net (code "15") (name "HDMI0_TX2P_PORT") (class "Default")
      (node (ref "ED5000") (pin "1") (pinfunction "IO1_1") (pintype "passive"))
      (node (ref "ED5000") (pin "10") (pinfunction "NC_10_10") (pintype "passive"))
      (node (ref "J5000") (pin "1") (pinfunction "D2P_1") (pintype "passive"))
    )
    (net (code "16") (name "HDMI0_TX3N_PORT") (class "Default")
      (node (ref "ED5001") (pin "5") (pinfunction "IO4_5") (pintype "passive"))
      (node (ref "ED5001") (pin "6") (pinfunction "NC_6_6") (pintype "passive"))
      (node (ref "J5000") (pin "12") (pinfunction "CLKN_12") (pintype "passive"))
    )
    (net (code "17") (name "HDMI0_TX3P_PORT") (class "Default")
      (node (ref "ED5001") (pin "4") (pinfunction "IO3_4") (pintype "passive"))
      (node (ref "ED5001") (pin "7") (pinfunction "NC_7_7") (pintype "passive"))
      (node (ref "J5000") (pin "10") (pinfunction "CLKP_10") (pintype "passive"))
    )
    (net (code "18") (name "HDMI1_TX0N_PORT") (class "Default")
      (node (ref "ED5007") (pin "2") (pinfunction "IO2_2") (pintype "passive"))
      (node (ref "ED5007") (pin "9") (pinfunction "NC_9_9") (pintype "passive"))
      (node (ref "J5001") (pin "9") (pinfunction "D0N_9") (pintype "passive"))
    )
    (net (code "19") (name "HDMI1_TX0P_PORT") (class "Default")
      (node (ref "ED5007") (pin "1") (pinfunction "IO1_1") (pintype "passive"))
      (node (ref "ED5007") (pin "10") (pinfunction "NC_10_10") (pintype "passive"))
      (node (ref "J5001") (pin "7") (pinfunction "D0P_7") (pintype "passive"))
    )
    (net (code "20") (name "HDMI1_TX1N_PORT") (class "Default")
      (node (ref "ED5006") (pin "5") (pinfunction "IO4_5") (pintype "passive"))
      (node (ref "ED5006") (pin "6") (pinfunction "NC_6_6") (pintype "passive"))
      (node (ref "J5001") (pin "6") (pinfunction "D1N_6") (pintype "passive"))
    )
    (net (code "21") (name "HDMI1_TX1P_PORT") (class "Default")
      (node (ref "ED5006") (pin "4") (pinfunction "IO3_4") (pintype "passive"))
      (node (ref "ED5006") (pin "7") (pinfunction "NC_7_7") (pintype "passive"))
      (node (ref "J5001") (pin "4") (pinfunction "D1P_4") (pintype "passive"))
    )
    (net (code "22") (name "HDMI1_TX2N_PORT") (class "Default")
      (node (ref "ED5006") (pin "2") (pinfunction "IO2_2") (pintype "passive"))
      (node (ref "ED5006") (pin "9") (pinfunction "NC_9_9") (pintype "passive"))
      (node (ref "J5001") (pin "3") (pinfunction "D2N_3") (pintype "passive"))
    )
    (net (code "23") (name "HDMI1_TX2P_PORT") (class "Default")
      (node (ref "ED5006") (pin "1") (pinfunction "IO1_1") (pintype "passive"))
      (node (ref "ED5006") (pin "10") (pinfunction "NC_10_10") (pintype "passive"))
      (node (ref "J5001") (pin "1") (pinfunction "D2P_1") (pintype "passive"))
    )
    (net (code "24") (name "HDMI1_TX3N_PORT") (class "Default")
      (node (ref "ED5007") (pin "5") (pinfunction "IO4_5") (pintype "passive"))
      (node (ref "ED5007") (pin "6") (pinfunction "NC_6_6") (pintype "passive"))
      (node (ref "J5001") (pin "12") (pinfunction "CLKN_12") (pintype "passive"))
    )
    (net (code "25") (name "HDMI1_TX3P_PORT") (class "Default")
      (node (ref "ED5007") (pin "4") (pinfunction "IO3_4") (pintype "passive"))
      (node (ref "ED5007") (pin "7") (pinfunction "NC_7_7") (pintype "passive"))
      (node (ref "J5001") (pin "10") (pinfunction "CLKP_10") (pintype "passive"))
    )
    (net (code "26") (name "HDMITX0_CEC_M0") (class "Default")
      (node (ref "R5011") (pin "1") (pinfunction "1_1") (pintype "passive"))
    )
    (net (code "27") (name "HDMITX0_HPDIN_M0") (class "Default")
      (node (ref "Q5006") (pin "3") (pinfunction "COLLECTOR_3") (pintype "passive"))
      (node (ref "R5000") (pin "2") (pinfunction "2_2") (pintype "passive"))
    )
    (net (code "28") (name "HDMITX0_SCL_M0") (class "Default")
      (node (ref "R5003") (pin "1") (pinfunction "1_1") (pintype "passive"))
    )
    (net (code "29") (name "HDMITX0_SDA_M0") (class "Default")
      (node (ref "R5008") (pin "1") (pinfunction "1_1") (pintype "passive"))
    )
    (net (code "30") (name "HDMITX1_CEC_M2") (class "Default")
      (node (ref "R5023") (pin "1") (pinfunction "1_1") (pintype "passive"))
    )
    (net (code "31") (name "HDMITX1_HPDIN_M0") (class "Default")
      (node (ref "Q5008") (pin "3") (pinfunction "COLLECTOR_3") (pintype "passive"))
      (node (ref "R5014") (pin "2") (pinfunction "2_2") (pintype "passive"))
    )
    (net (code "32") (name "HDMITX1_SCL_M1") (class "Default")
      (node (ref "R5015") (pin "1") (pinfunction "1_1") (pintype "passive"))
    )
    (net (code "33") (name "HDMITX1_SDA_M1") (class "Default")
      (node (ref "R5020") (pin "1") (pinfunction "1_1") (pintype "passive"))
    )
    (net (code "34") (name "Net-(D5000-K)") (class "Default")
      (node (ref "D5000") (pin "2") (pinfunction "K_2") (pintype "passive"))
      (node (ref "R5001") (pin "1") (pinfunction "1_1") (pintype "passive"))
      (node (ref "R5007") (pin "1") (pinfunction "1_1") (pintype "passive"))
    )
    (net (code "35") (name "Net-(D5003-K)") (class "Default")
      (node (ref "D5003") (pin "2") (pinfunction "K_2") (pintype "passive"))
      (node (ref "R5013") (pin "1") (pinfunction "1_1") (pintype "passive"))
      (node (ref "R5019") (pin "1") (pinfunction "1_1") (pintype "passive"))
    )
    (net (code "36") (name "Net-(Q5000-SOURCE)") (class "Default")
      (node (ref "Q5000") (pin "2") (pinfunction "SOURCE_2") (pintype "passive"))
      (node (ref "R5002") (pin "2") (pinfunction "2_2") (pintype "passive"))
      (node (ref "R5003") (pin "2") (pinfunction "2_2") (pintype "passive"))
    )
    (net (code "37") (name "Net-(Q5001-GATE)") (class "Default")
      (node (ref "C5003") (pin "1") (pinfunction "1_1") (pintype "passive"))
      (node (ref "Q5001") (pin "1") (pinfunction "GATE_1") (pintype "passive"))
      (node (ref "R5025") (pin "2") (pinfunction "2_2") (pintype "passive"))
    )
    (net (code "38") (name "Net-(Q5001-SOURCE)") (class "Default")
      (node (ref "C5003") (pin "2") (pinfunction "2_2") (pintype "passive"))
      (node (ref "Q5001") (pin "2") (pinfunction "SOURCE_2") (pintype "passive"))
      (node (ref "R5006") (pin "2") (pinfunction "2_2") (pintype "passive"))
      (node (ref "R5008") (pin "2") (pinfunction "2_2") (pintype "passive"))
    )
    (net (code "39") (name "Net-(Q5002-SOURCE)") (class "Default")
      (node (ref "Q5002") (pin "2") (pinfunction "SOURCE_2") (pintype "passive"))
      (node (ref "R5009") (pin "2") (pinfunction "2_2") (pintype "passive"))
      (node (ref "R5011") (pin "2") (pinfunction "2_2") (pintype "passive"))
    )
    (net (code "40") (name "Net-(Q5003-SOURCE)") (class "Default")
      (node (ref "Q5003") (pin "2") (pinfunction "SOURCE_2") (pintype "passive"))
      (node (ref "R5012") (pin "2") (pinfunction "2_2") (pintype "passive"))
      (node (ref "R5015") (pin "2") (pinfunction "2_2") (pintype "passive"))
    )
    (net (code "41") (name "Net-(Q5004-GATE)") (class "Default")
      (node (ref "C5005") (pin "1") (pinfunction "1_1") (pintype "passive"))
      (node (ref "Q5004") (pin "1") (pinfunction "GATE_1") (pintype "passive"))
      (node (ref "R5026") (pin "2") (pinfunction "2_2") (pintype "passive"))
    )
    (net (code "42") (name "Net-(Q5004-SOURCE)") (class "Default")
      (node (ref "C5005") (pin "2") (pinfunction "2_2") (pintype "passive"))
      (node (ref "Q5004") (pin "2") (pinfunction "SOURCE_2") (pintype "passive"))
      (node (ref "R5018") (pin "2") (pinfunction "2_2") (pintype "passive"))
      (node (ref "R5020") (pin "2") (pinfunction "2_2") (pintype "passive"))
    )
    (net (code "43") (name "Net-(Q5005-SOURCE)") (class "Default")
      (node (ref "Q5005") (pin "2") (pinfunction "SOURCE_2") (pintype "passive"))
      (node (ref "R5021") (pin "2") (pinfunction "2_2") (pintype "passive"))
      (node (ref "R5023") (pin "2") (pinfunction "2_2") (pintype "passive"))
    )
    (net (code "44") (name "Net-(Q5006-BASE)") (class "Default")
      (node (ref "Q5006") (pin "1") (pinfunction "BASE_1") (pintype "passive"))
      (node (ref "Q5007") (pin "3") (pinfunction "COLLECTOR_3") (pintype "passive"))
      (node (ref "R5005") (pin "2") (pinfunction "2_2") (pintype "passive"))
    )
    (net (code "45") (name "Net-(Q5007-BASE)") (class "Default")
      (node (ref "Q5007") (pin "1") (pinfunction "BASE_1") (pintype "passive"))
      (node (ref "R5004") (pin "1") (pinfunction "1_1") (pintype "passive"))
      (node (ref "R5027") (pin "1") (pinfunction "1_1") (pintype "passive"))
    )
    (net (code "46") (name "Net-(Q5008-BASE)") (class "Default")
      (node (ref "Q5008") (pin "1") (pinfunction "BASE_1") (pintype "passive"))
      (node (ref "Q5009") (pin "3") (pinfunction "COLLECTOR_3") (pintype "passive"))
      (node (ref "R5017") (pin "2") (pinfunction "2_2") (pintype "passive"))
    )
    (net (code "47") (name "Net-(Q5009-BASE)") (class "Default")
      (node (ref "Q5009") (pin "1") (pinfunction "BASE_1") (pintype "passive"))
      (node (ref "R5016") (pin "1") (pinfunction "1_1") (pintype "passive"))
      (node (ref "R5028") (pin "1") (pinfunction "1_1") (pintype "passive"))
    )
    (net (code "48") (name "VCC5V0_SYS") (class "Default")
      (node (ref "D5000") (pin "1") (pinfunction "A_1") (pintype "passive"))
      (node (ref "D5002") (pin "1") (pinfunction "A_1") (pintype "passive"))
      (node (ref "D5003") (pin "1") (pinfunction "A_1") (pintype "passive"))
      (node (ref "D5005") (pin "1") (pinfunction "A_1") (pintype "passive"))
      (node (ref "Q5002") (pin "1") (pinfunction "GATE_1") (pintype "passive"))
      (node (ref "Q5005") (pin "1") (pinfunction "GATE_1") (pintype "passive"))
      (node (ref "R5010") (pin "1") (pinfunction "1_1") (pintype "passive"))
      (node (ref "R5022") (pin "1") (pinfunction "1_1") (pintype "passive"))
    )
    (net (code "49") (name "VCC5V_HDMI_TX0") (class "Default")
      (node (ref "C5000") (pin "1") (pinfunction "1_1") (pintype "passive"))
      (node (ref "D5002") (pin "2") (pinfunction "K_2") (pintype "passive"))
      (node (ref "J5000") (pin "18") (pinfunction "+5V_18") (pintype "passive"))
      (node (ref "R5010") (pin "2") (pinfunction "2_2") (pintype "passive"))
    )
    (net (code "50") (name "VCC5V_HDMI_TX1") (class "Default")
      (node (ref "C5001") (pin "1") (pinfunction "1_1") (pintype "passive"))
      (node (ref "D5005") (pin "2") (pinfunction "K_2") (pintype "passive"))
      (node (ref "J5001") (pin "18") (pinfunction "+5V_18") (pintype "passive"))
      (node (ref "R5022") (pin "2") (pinfunction "2_2") (pintype "passive"))
    )
    (net (code "51") (name "VCC_1V8") (class "Default")
      (node (ref "R5000") (pin "1") (pinfunction "1_1") (pintype "passive"))
      (node (ref "R5005") (pin "1") (pinfunction "1_1") (pintype "passive"))
      (node (ref "R5014") (pin "1") (pinfunction "1_1") (pintype "passive"))
      (node (ref "R5017") (pin "1") (pinfunction "1_1") (pintype "passive"))
    )
    (net (code "52") (name "VCC_3V3") (class "Default")
      (node (ref "Q5000") (pin "1") (pinfunction "GATE_1") (pintype "passive"))
      (node (ref "Q5003") (pin "1") (pinfunction "GATE_1") (pintype "passive"))
      (node (ref "R5002") (pin "1") (pinfunction "1_1") (pintype "passive"))
      (node (ref "R5006") (pin "1") (pinfunction "1_1") (pintype "passive"))
      (node (ref "R5009") (pin "1") (pinfunction "1_1") (pintype "passive"))
      (node (ref "R5012") (pin "1") (pinfunction "1_1") (pintype "passive"))
      (node (ref "R5018") (pin "1") (pinfunction "1_1") (pintype "passive"))
      (node (ref "R5021") (pin "1") (pinfunction "1_1") (pintype "passive"))
      (node (ref "R5025") (pin "1") (pinfunction "1_1") (pintype "passive"))
      (node (ref "R5026") (pin "1") (pinfunction "1_1") (pintype "passive"))
    )
    (net (code "53") (name "unconnected-(J5000-Utility-Pad14)") (class "Default")
      (node (ref "J5000") (pin "14") (pinfunction "Utility_14") (pintype "passive+no_connect"))
    )
    (net (code "54") (name "unconnected-(J5001-Utility-Pad14)") (class "Default")
      (node (ref "J5001") (pin "14") (pinfunction "Utility_14") (pintype "passive+no_connect"))
    )
  )
)
